# PCB.net
KiCad netlist of a schematic drawn in EasyEDA Pro
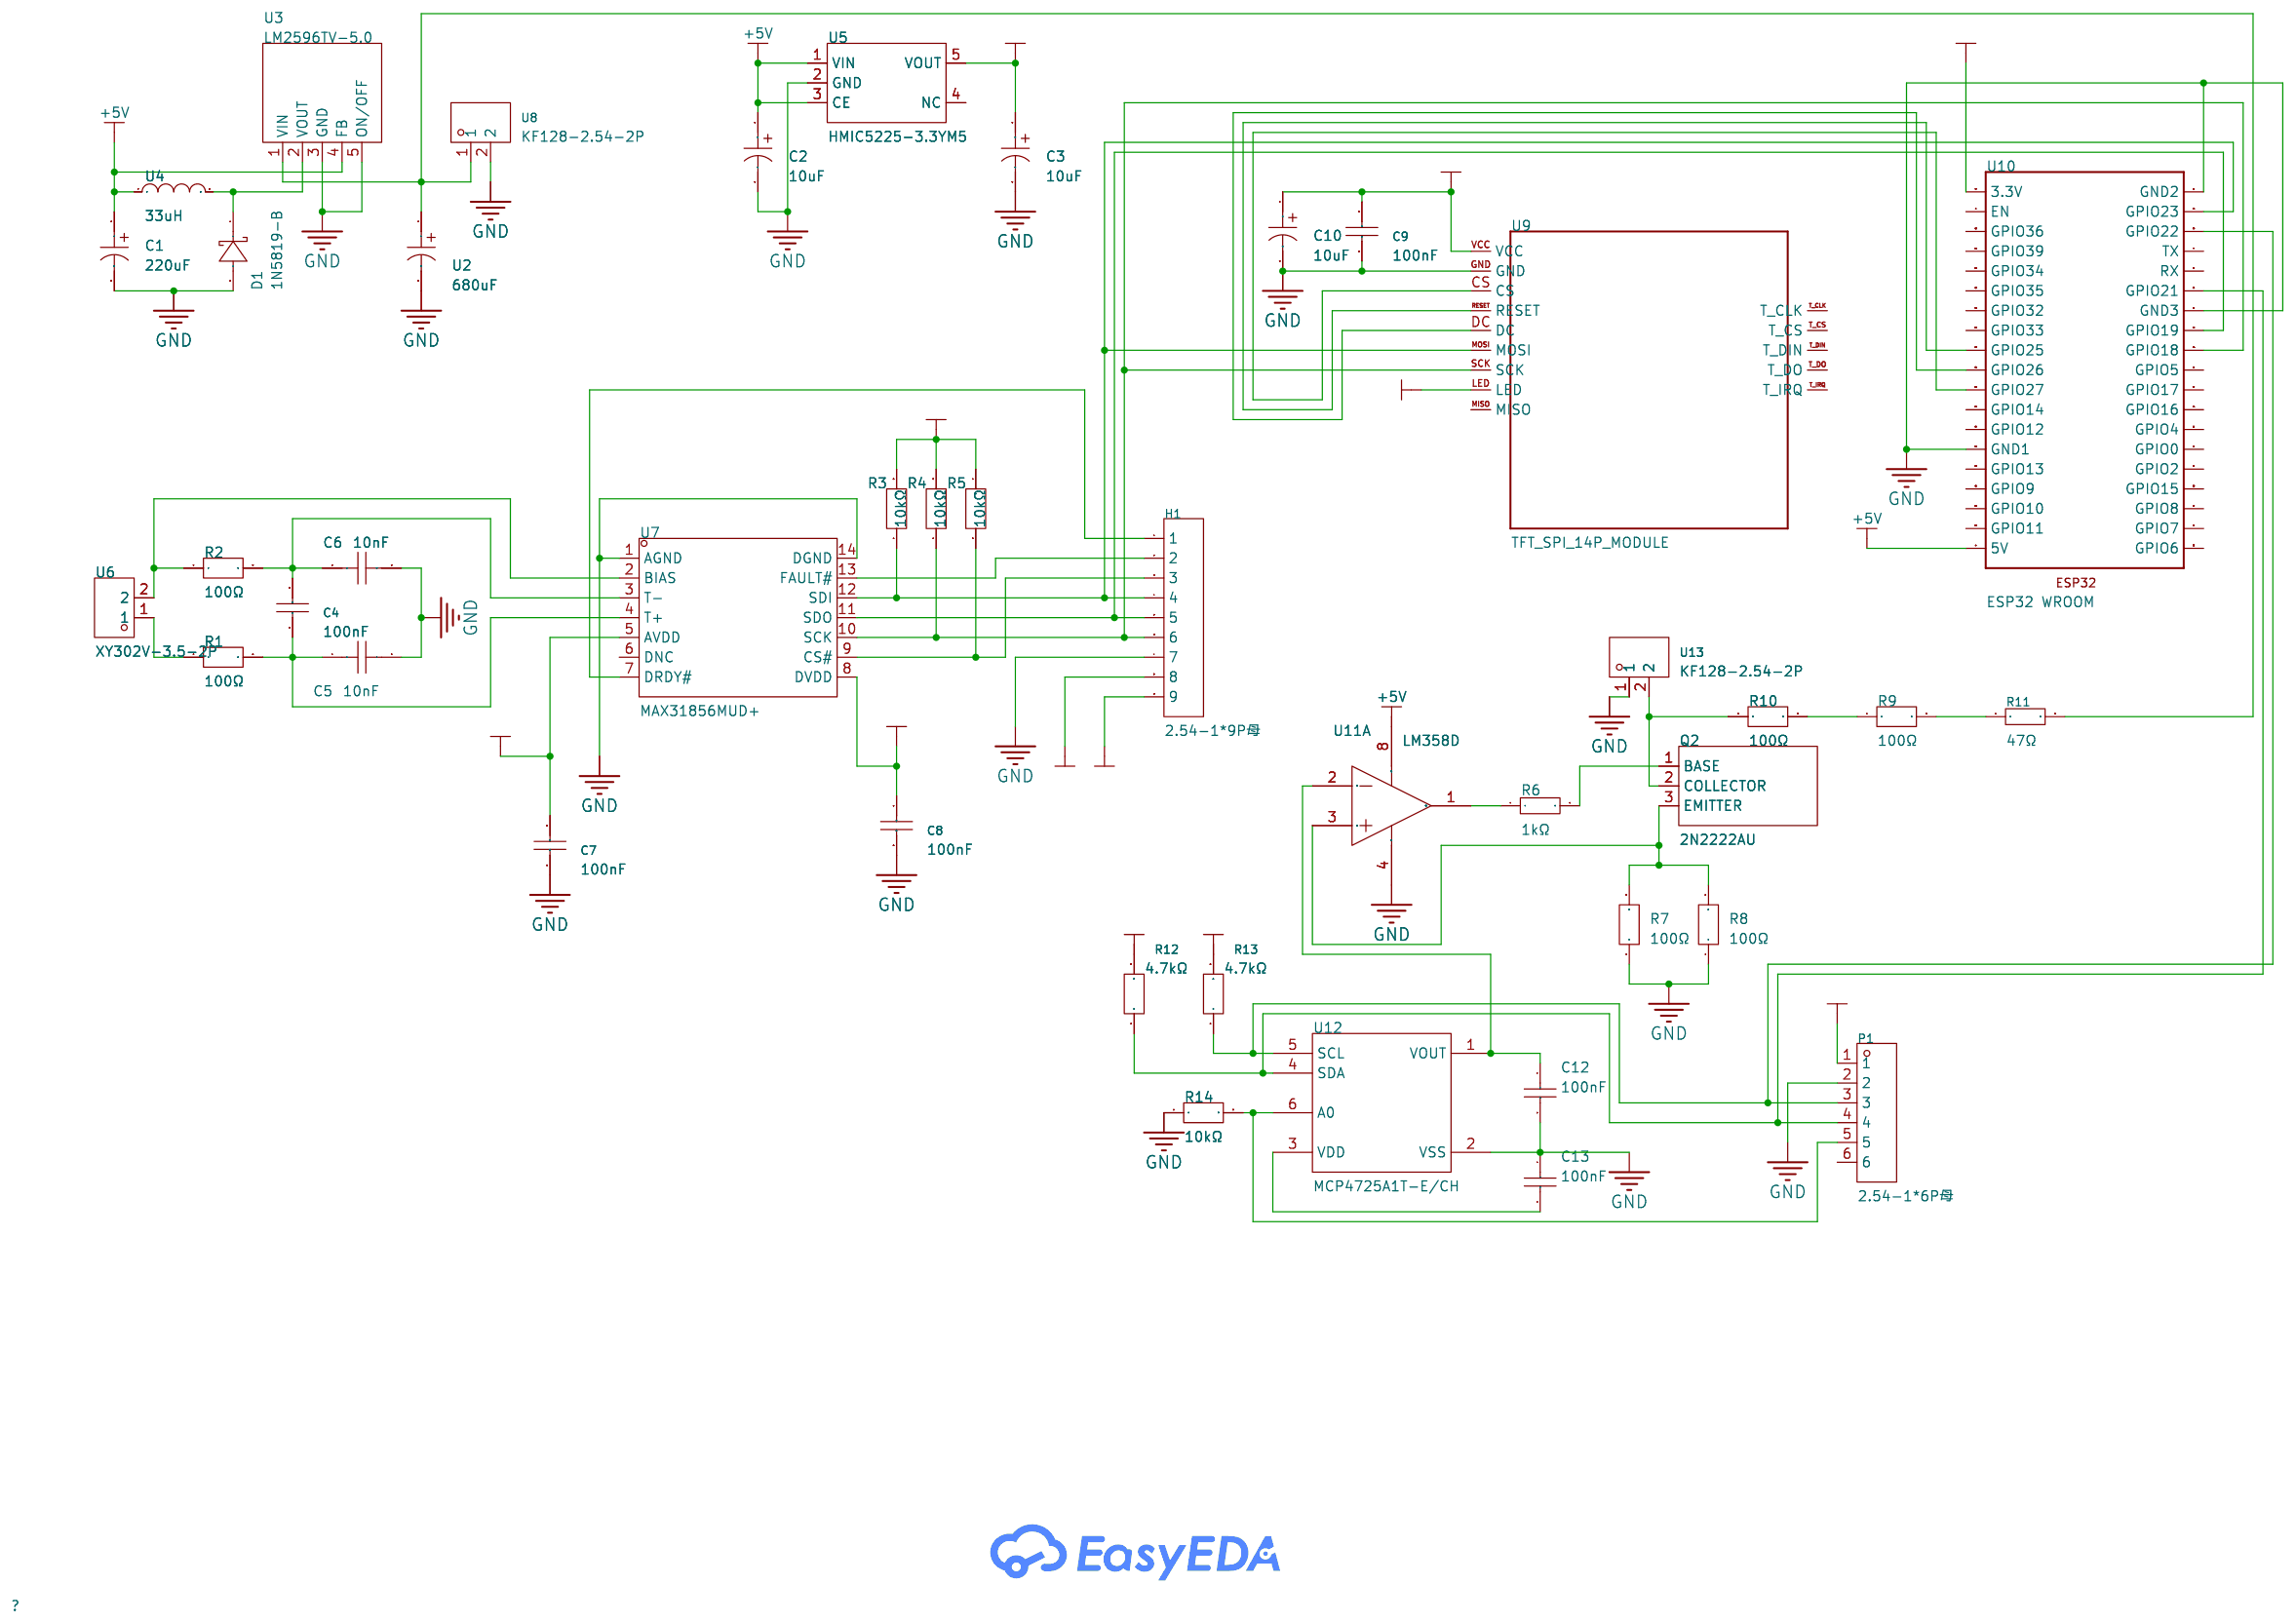
[diagram p0: schematic sheet]

(export (version "E")
  (design (tool "Eeschema 10.0.6"))
  (components
    (comp (ref "C1")
      (value "220uF")
      (footprint "easyedapro:CAP-TH_BD10.0-P5.00-D1.0-FD")
      (fields
        (field (name "Manufacturer Part") "220uF50V10x13GF")
        (field (name "Manufacturer") "Econd(米朗电子)")
      )
      (libsource (lib "easyedapro") (part "220UF50V10X13GF"))
    )
    (comp (ref "C2")
      (value "10uF")
      (footprint "easyedapro:CAP-TH_BD5.0-P2.00-D0.8-FD-10UF50VC110GL")
      (fields (field (name "Manufacturer Part") "10UF50VC110GL") (field (name "Manufacturer") "Econd(米朗电子)"))
      (libsource (lib "easyedapro") (part "10UF50VC110GL"))
    )
    (comp (ref "C3")
      (value "10uF")
      (footprint "easyedapro:CAP-TH_BD5.0-P2.00-D0.8-FD-10UF50VC110GL")
      (fields (field (name "Manufacturer Part") "10UF50VC110GL") (field (name "Manufacturer") "Econd(米朗电子)"))
      (libsource (lib "easyedapro") (part "10UF50VC110GL"))
    )
    (comp (ref "C4")
      (value "100nF")
      (footprint "easyedapro:C0805")
      (description "Capacitance:100nF Tolerance:±10% Tolerance:±10% Voltage Rating:50V Temperature Coefficient:X7R")
      (fields (field (name "Manufacturer Part") "0805B104K500NT") (field (name "Manufacturer") "FH(风华)"))
      (libsource (lib "easyedapro") (part "0805B104K500NT"))
    )
    (comp (ref "C5")
      (value "10nF")
      (footprint "easyedapro:C0402")
      (description "Capacitance:10nF Tolerance:±10% Tolerance:±10% Voltage Rating:50V Temperature Coefficient:X7R")
      (fields
        (field (name "Manufacturer Part") "FCC0402B103K500AT")
        (field (name "Manufacturer") "FOJAN(富捷)")
      )
      (libsource (lib "easyedapro") (part "FCC0402B103K500AT"))
    )
    (comp (ref "C6")
      (value "10nF")
      (footprint "easyedapro:C0402")
      (description "Capacitance:10nF Tolerance:±10% Tolerance:±10% Voltage Rating:50V Temperature Coefficient:X7R")
      (fields
        (field (name "Manufacturer Part") "FCC0402B103K500AT")
        (field (name "Manufacturer") "FOJAN(富捷)")
      )
      (libsource (lib "easyedapro") (part "FCC0402B103K500AT"))
    )
    (comp (ref "C7")
      (value "100nF")
      (footprint "easyedapro:C0805")
      (description "Capacitance:100nF Tolerance:±10% Tolerance:±10% Voltage Rating:50V Temperature Coefficient:X7R")
      (fields (field (name "Manufacturer Part") "0805B104K500NT") (field (name "Manufacturer") "FH(风华)"))
      (libsource (lib "easyedapro") (part "0805B104K500NT"))
    )
    (comp (ref "C8")
      (value "100nF")
      (footprint "easyedapro:C0805")
      (description "Capacitance:100nF Tolerance:±10% Tolerance:±10% Voltage Rating:50V Temperature Coefficient:X7R")
      (fields (field (name "Manufacturer Part") "0805B104K500NT") (field (name "Manufacturer") "FH(风华)"))
      (libsource (lib "easyedapro") (part "0805B104K500NT"))
    )
    (comp (ref "C9")
      (value "100nF")
      (footprint "easyedapro:C0805")
      (description "Capacitance:100nF Tolerance:±10% Tolerance:±10% Voltage Rating:50V Temperature Coefficient:X7R")
      (fields (field (name "Manufacturer Part") "0805B104K500NT") (field (name "Manufacturer") "FH(风华)"))
      (libsource (lib "easyedapro") (part "0805B104K500NT"))
    )
    (comp (ref "C10")
      (value "10uF")
      (footprint "easyedapro:CAP-TH_BD5.0-P2.00-D0.8-FD-10UF50VC110GL")
      (fields (field (name "Manufacturer Part") "10UF50VC110GL") (field (name "Manufacturer") "Econd(米朗电子)"))
      (libsource (lib "easyedapro") (part "10UF50VC110GL"))
    )
    (comp (ref "C12")
      (value "100nF")
      (footprint "easyedapro:C0402")
      (description "Capacitance:100nF Tolerance:±10% Tolerance:±10% Voltage Rating:50V Temperature Coefficient:X7R")
      (fields (field (name "Manufacturer Part") "0402B104K500NT") (field (name "Manufacturer") "FH(风华)"))
      (libsource (lib "easyedapro") (part "0402B104K500NT"))
    )
    (comp (ref "C13")
      (value "100nF")
      (footprint "easyedapro:C0402")
      (description "Capacitance:100nF Tolerance:±10% Tolerance:±10% Voltage Rating:50V Temperature Coefficient:X7R")
      (fields (field (name "Manufacturer Part") "0402B104K500NT") (field (name "Manufacturer") "FH(风华)"))
      (libsource (lib "easyedapro") (part "0402B104K500NT"))
    )
    (comp (ref "D1")
      (value "1N5819-B")
      (footprint "easyedapro:DO-41_BD2.4-L4.7-P8.70-D0.6-RD")
      (fields (field (name "Manufacturer") "GOODWORK(固得沃克)"))
      (libsource (lib "easyedapro") (part "1N5819-B"))
    )
    (comp (ref "H1")
      (value "2.54-1*9P母")
      (footprint "easyedapro:HDR-TH_9P-P2.54-V-F-1")
      (fields (field (name "Manufacturer") "BOOMELE(博穆精密)"))
      (libsource (lib "easyedapro") (part "Header-Female-2.54_1x9"))
    )
    (comp (ref "P1")
      (value "2.54-1*6P母")
      (footprint "easyedapro:HDR-TH_6P-P2.54-V-F")
      (fields (field (name "Manufacturer") "BOOMELE(博穆精密)"))
      (libsource (lib "easyedapro") (part "Header-Female-2.54_1x6"))
    )
    (comp (ref "Q2")
      (value "2N2222AU")
      (footprint "easyedapro:SOT-89-3_L4.5-W2.4-P1.50-LS4.0-BR")
      (fields (field (name "Manufacturer") "CBI(创基)"))
      (libsource (lib "easyedapro") (part "2N2222AU"))
    )
    (comp (ref "R1")
      (value "100Ω")
      (footprint "easyedapro:R0603")
      (fields (field (name "Manufacturer Part") "FRC0603F1000TS") (field (name "Manufacturer") "FOJAN(富捷)"))
      (libsource (lib "easyedapro") (part "FRC0603F1000TS"))
    )
    (comp (ref "R2")
      (value "100Ω")
      (footprint "easyedapro:R0603")
      (fields (field (name "Manufacturer Part") "FRC0603F1000TS") (field (name "Manufacturer") "FOJAN(富捷)"))
      (libsource (lib "easyedapro") (part "FRC0603F1000TS"))
    )
    (comp (ref "R3")
      (value "10kΩ")
      (footprint "easyedapro:R0805")
      (fields (field (name "Manufacturer Part") "FRC0805J103TS") (field (name "Manufacturer") "FOJAN(富捷)"))
      (libsource (lib "easyedapro") (part "FRC0805J103TS"))
    )
    (comp (ref "R4")
      (value "10kΩ")
      (footprint "easyedapro:R0805")
      (fields (field (name "Manufacturer Part") "FRC0805J103TS") (field (name "Manufacturer") "FOJAN(富捷)"))
      (libsource (lib "easyedapro") (part "FRC0805J103TS"))
    )
    (comp (ref "R5")
      (value "10kΩ")
      (footprint "easyedapro:R0805")
      (fields (field (name "Manufacturer Part") "FRC0805J103TS") (field (name "Manufacturer") "FOJAN(富捷)"))
      (libsource (lib "easyedapro") (part "FRC0805J103TS"))
    )
    (comp (ref "R6")
      (value "1kΩ")
      (footprint "easyedapro:R0402")
      (fields (field (name "Manufacturer Part") "RC0402FR-071KL") (field (name "Manufacturer") "YAGEO(国巨)"))
      (libsource (lib "easyedapro") (part "RC0402FR-071KL"))
    )
    (comp (ref "R7")
      (value "100Ω")
      (footprint "easyedapro:R0603")
      (fields (field (name "Manufacturer Part") "FRC0603F1000TS") (field (name "Manufacturer") "FOJAN(富捷)"))
      (libsource (lib "easyedapro") (part "FRC0603F1000TS"))
    )
    (comp (ref "R8")
      (value "100Ω")
      (footprint "easyedapro:R0603")
      (fields (field (name "Manufacturer Part") "FRC0603F1000TS") (field (name "Manufacturer") "FOJAN(富捷)"))
      (libsource (lib "easyedapro") (part "FRC0603F1000TS"))
    )
    (comp (ref "R9")
      (value "100Ω")
      (footprint "easyedapro:R0603")
      (fields (field (name "Manufacturer Part") "FRC0603F1000TS") (field (name "Manufacturer") "FOJAN(富捷)"))
      (libsource (lib "easyedapro") (part "FRC0603F1000TS"))
    )
    (comp (ref "R10")
      (value "100Ω")
      (footprint "easyedapro:R0603")
      (fields (field (name "Manufacturer Part") "FRC0603F1000TS") (field (name "Manufacturer") "FOJAN(富捷)"))
      (libsource (lib "easyedapro") (part "FRC0603F1000TS"))
    )
    (comp (ref "R11")
      (value "47Ω")
      (footprint "easyedapro:R0603")
      (fields
        (field (name "Manufacturer Part") "0603WAF470JT5E")
        (field (name "Manufacturer") "UNI-ROYAL(厚声)")
      )
      (libsource (lib "easyedapro") (part "0603WAF470JT5E"))
    )
    (comp (ref "R12")
      (value "4.7kΩ")
      (footprint "easyedapro:R0603")
      (fields (field (name "Manufacturer Part") "FRC0603J472 TS") (field (name "Manufacturer") "FOJAN(富捷)"))
      (libsource (lib "easyedapro") (part "FRC0603J472 TS"))
    )
    (comp (ref "R13")
      (value "4.7kΩ")
      (footprint "easyedapro:R0603")
      (fields (field (name "Manufacturer Part") "FRC0603J472 TS") (field (name "Manufacturer") "FOJAN(富捷)"))
      (libsource (lib "easyedapro") (part "FRC0603J472 TS"))
    )
    (comp (ref "R14")
      (value "10kΩ")
      (footprint "easyedapro:R0805")
      (fields (field (name "Manufacturer Part") "FRC0805J103TS") (field (name "Manufacturer") "FOJAN(富捷)"))
      (libsource (lib "easyedapro") (part "FRC0805J103TS"))
    )
    (comp (ref "U2")
      (value "680uF")
      (footprint "easyedapro:CAP-TH_BD13.0-P5.00-D0.6-FD")
      (fields
        (field (name "Manufacturer Part") "SHF680UF50V03EC1055")
        (field (name "Manufacturer") "KNSCHA(科尼盛)")
      )
      (libsource (lib "easyedapro") (part "SHF680UF50V03EC1055"))
    )
    (comp (ref "U3")
      (value "LM2596TV-5.0")
      (footprint "easyedapro:TO-220-5_L10.2-W4.5-P1.70-TL")
      (fields (field (name "Manufacturer") "HTC"))
      (libsource (lib "easyedapro") (part "LM2596TV-5.0"))
    )
    (comp (ref "U4")
      (value "33uH")
      (footprint "easyedapro:IND-TH_L7.0-W4.0-P5.0")
      (fields (field (name "Manufacturer Part") "2727-07H") (field (name "Manufacturer") "API Delevan"))
      (libsource (lib "easyedapro") (part "2727-07H"))
    )
    (comp (ref "U5")
      (value "HMIC5225-3.3YM5")
      (footprint "easyedapro:SOT-23-5_L3.0-W1.7-P0.95-LS2.8-BL")
      (fields (field (name "Manufacturer") "HXY MOSFET(华轩阳电子)"))
      (libsource (lib "easyedapro") (part "HMIC5225-3.3YM5"))
    )
    (comp (ref "U6")
      (value "XY302V-3.5-2P")
      (footprint "easyedapro:CONN-TH_XY302V-3.5-2P")
      (fields (field (name "Manufacturer") "XINLAIYA(新莱亚)"))
      (libsource (lib "easyedapro") (part "XY302V-3.5-2P"))
    )
    (comp (ref "U7")
      (value "MAX31856MUD+")
      (footprint "easyedapro:TSSOP-14_L5.0-W4.4-P0.65-LS6.4-BL")
      (fields (field (name "Manufacturer") "ADI(亚德诺)/MAXIM(美信)"))
      (libsource (lib "easyedapro") (part "MAX31856MUD+"))
    )
    (comp (ref "U8")
      (value "KF128-2.54-2P")
      (footprint "easyedapro:CONN-TH_P2.54_KF128-2.54-2P")
      (fields (field (name "Manufacturer") "KEFA(科发)"))
      (libsource (lib "easyedapro") (part "KF128-2.54-2P"))
    )
    (comp (ref "U9")
      (value "TFT_SPI_14P_MODULE")
      (footprint "easyedapro:TFT_2_4_SPI_MODULE")
      (libsource (lib "easyedapro") (part "TFT_SPI_14P_MODULE"))
    )
    (comp (ref "U10")
      (value "ESP32 WROOM")
      (footprint "easyedapro:ESP32")
      (libsource (lib "easyedapro") (part "ESP32"))
    )
    (comp (ref "U11")
      (value "LM358D")
      (footprint "easyedapro:SO-8_L4.9-W3.9-P1.27-LS5.9-BL")
      (fields (field (name "Manufacturer") "ST(意法半导体)"))
      (libsource (lib "easyedapro") (part "LM358D_C2936099"))
    )
    (comp (ref "U12")
      (value "MCP4725A1T-E/CH")
      (footprint "easyedapro:SOT-23-6_L2.9-W1.6-P0.95-LS2.8-BR")
      (fields (field (name "Manufacturer") "MICROCHIP(美国微芯)"))
      (libsource (lib "easyedapro") (part "MCP4725A1T-E/CH"))
    )
    (comp (ref "U13")
      (value "KF128-2.54-2P")
      (footprint "easyedapro:CONN-TH_P2.54_KF128-2.54-2P")
      (fields (field (name "Manufacturer") "KEFA(科发)"))
      (libsource (lib "easyedapro") (part "KF128-2.54-2P"))
    )
  )
  (nets
    (net (code "1") (name "+3.3V") (class "Default")
      (node (ref "C10") (pin "1") (pinfunction "1_1") (pintype "input"))
      (node (ref "C3") (pin "1") (pinfunction "1_1") (pintype "input"))
      (node (ref "C7") (pin "1") (pinfunction "1_1") (pintype "input"))
      (node (ref "C8") (pin "1") (pinfunction "1_1") (pintype "input"))
      (node (ref "C9") (pin "1") (pinfunction "1_1") (pintype "input"))
      (node (ref "H1") (pin "8") (pinfunction "8_8") (pintype "input"))
      (node (ref "P1") (pin "1") (pinfunction "1_1") (pintype "input"))
      (node (ref "R12") (pin "2") (pinfunction "2_2") (pintype "input"))
      (node (ref "R13") (pin "2") (pinfunction "2_2") (pintype "input"))
      (node (ref "R3") (pin "2") (pinfunction "2_2") (pintype "unspecified"))
      (node (ref "R4") (pin "2") (pinfunction "2_2") (pintype "unspecified"))
      (node (ref "R5") (pin "1") (pinfunction "1_1") (pintype "unspecified"))
      (node (ref "U10") (pin "3.3V") (pinfunction "3.3V_3.3V") (pintype "bidirectional"))
      (node (ref "U5") (pin "5") (pinfunction "VOUT_5") (pintype "unspecified"))
      (node (ref "U7") (pin "5") (pinfunction "AVDD_5") (pintype "unspecified"))
      (node (ref "U7") (pin "8") (pinfunction "DVDD_8") (pintype "unspecified"))
      (node (ref "U9") (pin "LED") (pinfunction "LED_LED") (pintype "input"))
      (node (ref "U9") (pin "VCC") (pinfunction "VCC_VCC") (pintype "unspecified"))
    )
    (net (code "2") (name "+5V") (class "Default")
      (node (ref "C1") (pin "1") (pinfunction "1_1") (pintype "input"))
      (node (ref "C2") (pin "1") (pinfunction "1_1") (pintype "input"))
      (node (ref "U10") (pin "5V") (pinfunction "5V_5V") (pintype "bidirectional"))
      (node (ref "U11") (pin "8") (pinfunction "VCC+_8") (pintype "unspecified"))
      (node (ref "U3") (pin "4") (pinfunction "FB_4") (pintype "unspecified"))
      (node (ref "U4") (pin "1") (pinfunction "1_1") (pintype "unspecified"))
      (node (ref "U5") (pin "1") (pinfunction "VIN_1") (pintype "unspecified"))
      (node (ref "U5") (pin "3") (pinfunction "CE_3") (pintype "unspecified"))
    )
    (net (code "3") (name "GND") (class "Default")
      (node (ref "C1") (pin "2") (pinfunction "2_2") (pintype "input"))
      (node (ref "C10") (pin "2") (pinfunction "2_2") (pintype "input"))
      (node (ref "C12") (pin "2") (pinfunction "2_2") (pintype "input"))
      (node (ref "C13") (pin "1") (pinfunction "1_1") (pintype "input"))
      (node (ref "C2") (pin "2") (pinfunction "2_2") (pintype "input"))
      (node (ref "C3") (pin "2") (pinfunction "2_2") (pintype "input"))
      (node (ref "C5") (pin "2") (pinfunction "2_2") (pintype "unspecified"))
      (node (ref "C6") (pin "2") (pinfunction "2_2") (pintype "unspecified"))
      (node (ref "C7") (pin "2") (pinfunction "2_2") (pintype "input"))
      (node (ref "C8") (pin "2") (pinfunction "2_2") (pintype "input"))
      (node (ref "C9") (pin "2") (pinfunction "2_2") (pintype "input"))
      (node (ref "D1") (pin "2") (pinfunction "A_2") (pintype "unspecified"))
      (node (ref "H1") (pin "7") (pinfunction "7_7") (pintype "input"))
      (node (ref "P1") (pin "2") (pinfunction "2_2") (pintype "input"))
      (node (ref "R14") (pin "1") (pinfunction "1_1") (pintype "unspecified"))
      (node (ref "R7") (pin "1") (pinfunction "1_1") (pintype "unspecified"))
      (node (ref "R8") (pin "1") (pinfunction "1_1") (pintype "unspecified"))
      (node (ref "U10") (pin "GND1") (pinfunction "GND1_GND1") (pintype "bidirectional"))
      (node (ref "U10") (pin "GND2") (pinfunction "GND2_GND2") (pintype "bidirectional"))
      (node (ref "U10") (pin "GND3") (pinfunction "GND3_GND3") (pintype "bidirectional"))
      (node (ref "U11") (pin "4") (pinfunction "VCC-_4") (pintype "unspecified"))
      (node (ref "U12") (pin "2") (pinfunction "VSS_2") (pintype "unspecified"))
      (node (ref "U13") (pin "1") (pinfunction "1_1") (pintype "input"))
      (node (ref "U2") (pin "2") (pinfunction "2_2") (pintype "input"))
      (node (ref "U3") (pin "3") (pinfunction "GND_3") (pintype "unspecified"))
      (node (ref "U3") (pin "5") (pinfunction "ON/OFF_5") (pintype "unspecified"))
      (node (ref "U5") (pin "2") (pinfunction "GND_2") (pintype "unspecified"))
      (node (ref "U7") (pin "1") (pinfunction "AGND_1") (pintype "unspecified"))
      (node (ref "U7") (pin "14") (pinfunction "DGND_14") (pintype "unspecified"))
      (node (ref "U8") (pin "2") (pinfunction "2_2") (pintype "input"))
      (node (ref "U9") (pin "GND") (pinfunction "GND_GND") (pintype "unspecified"))
    )
    (net (code "4") (name "Net-(D1-K)") (class "Default")
      (node (ref "D1") (pin "1") (pinfunction "K_1") (pintype "unspecified"))
      (node (ref "U3") (pin "2") (pinfunction "VOUT_2") (pintype "unspecified"))
      (node (ref "U4") (pin "2") (pinfunction "2_2") (pintype "unspecified"))
    )
    (net (code "5") (name "Net-(Q2-BASE)") (class "Default")
      (node (ref "Q2") (pin "1") (pinfunction "BASE_1") (pintype "unspecified"))
      (node (ref "R6") (pin "2") (pinfunction "2_2") (pintype "input"))
    )
    (net (code "6") (name "Net-(Q2-COLLECTOR)") (class "Default")
      (node (ref "Q2") (pin "2") (pinfunction "COLLECTOR_2") (pintype "unspecified"))
      (node (ref "R10") (pin "1") (pinfunction "1_1") (pintype "unspecified"))
      (node (ref "U13") (pin "2") (pinfunction "2_2") (pintype "input"))
    )
    (net (code "7") (name "Net-(Q2-EMITTER)") (class "Default")
      (node (ref "Q2") (pin "3") (pinfunction "EMITTER_3") (pintype "unspecified"))
      (node (ref "R7") (pin "2") (pinfunction "2_2") (pintype "unspecified"))
      (node (ref "R8") (pin "2") (pinfunction "2_2") (pintype "unspecified"))
      (node (ref "U11") (pin "3") (pinfunction "IN1+_3") (pintype "unspecified"))
    )
    (net (code "8") (name "Net-(R1-Pad1)") (class "Default")
      (node (ref "R1") (pin "1") (pinfunction "1_1") (pintype "unspecified"))
      (node (ref "U6") (pin "1") (pinfunction "1_1") (pintype "unspecified"))
    )
    (net (code "9") (name "Net-(R10-Pad2)") (class "Default")
      (node (ref "R10") (pin "2") (pinfunction "2_2") (pintype "unspecified"))
      (node (ref "R9") (pin "1") (pinfunction "1_1") (pintype "unspecified"))
    )
    (net (code "10") (name "Net-(R11-Pad1)") (class "Default")
      (node (ref "R11") (pin "1") (pinfunction "1_1") (pintype "input"))
      (node (ref "R9") (pin "2") (pinfunction "2_2") (pintype "unspecified"))
    )
    (net (code "11") (name "Net-(U3-VIN)") (class "Default")
      (node (ref "R11") (pin "2") (pinfunction "2_2") (pintype "input"))
      (node (ref "U2") (pin "1") (pinfunction "1_1") (pintype "input"))
      (node (ref "U3") (pin "1") (pinfunction "VIN_1") (pintype "unspecified"))
      (node (ref "U8") (pin "1") (pinfunction "1_1") (pintype "input"))
    )
    (net (code "12") (name "Net-(U7-BIAS)") (class "Default")
      (node (ref "R2") (pin "1") (pinfunction "1_1") (pintype "unspecified"))
      (node (ref "U6") (pin "2") (pinfunction "2_2") (pintype "unspecified"))
      (node (ref "U7") (pin "2") (pinfunction "BIAS_2") (pintype "unspecified"))
    )
    (net (code "13") (name "Net-(U7-CS#)") (class "Default")
      (node (ref "H1") (pin "3") (pinfunction "3_3") (pintype "input"))
      (node (ref "R5") (pin "2") (pinfunction "2_2") (pintype "unspecified"))
      (node (ref "U7") (pin "9") (pinfunction "CS#_9") (pintype "unspecified"))
    )
    (net (code "14") (name "Net-(U7-DRDY#)") (class "Default")
      (node (ref "H1") (pin "1") (pinfunction "1_1") (pintype "input"))
      (node (ref "U7") (pin "7") (pinfunction "DRDY#_7") (pintype "unspecified"))
    )
    (net (code "15") (name "Net-(U7-FAULT#)") (class "Default")
      (node (ref "H1") (pin "2") (pinfunction "2_2") (pintype "input"))
      (node (ref "U7") (pin "13") (pinfunction "FAULT#_13") (pintype "unspecified"))
    )
    (net (code "16") (name "Net-(U7-SCK)") (class "Default")
      (node (ref "H1") (pin "6") (pinfunction "6_6") (pintype "input"))
      (node (ref "R4") (pin "1") (pinfunction "1_1") (pintype "unspecified"))
      (node (ref "U10") (pin "GPIO18") (pinfunction "GPIO18_GPIO18") (pintype "bidirectional"))
      (node (ref "U7") (pin "10") (pinfunction "SCK_10") (pintype "unspecified"))
      (node (ref "U9") (pin "SCK") (pinfunction "SCK_SCK") (pintype "input"))
    )
    (net (code "17") (name "Net-(U7-SDI)") (class "Default")
      (node (ref "H1") (pin "4") (pinfunction "4_4") (pintype "input"))
      (node (ref "R3") (pin "1") (pinfunction "1_1") (pintype "unspecified"))
      (node (ref "U10") (pin "GPIO23") (pinfunction "GPIO23_GPIO23") (pintype "bidirectional"))
      (node (ref "U7") (pin "12") (pinfunction "SDI_12") (pintype "unspecified"))
      (node (ref "U9") (pin "MOSI") (pinfunction "MOSI_MOSI") (pintype "input"))
    )
    (net (code "18") (name "Net-(U7-SDO)") (class "Default")
      (node (ref "H1") (pin "5") (pinfunction "5_5") (pintype "input"))
      (node (ref "U10") (pin "GPIO19") (pinfunction "GPIO19_GPIO19") (pintype "bidirectional"))
      (node (ref "U7") (pin "11") (pinfunction "SDO_11") (pintype "unspecified"))
    )
    (net (code "19") (name "Net-(U7-T+)") (class "Default")
      (node (ref "C4") (pin "1") (pinfunction "1_1") (pintype "input"))
      (node (ref "C5") (pin "1") (pinfunction "1_1") (pintype "unspecified"))
      (node (ref "R1") (pin "2") (pinfunction "2_2") (pintype "unspecified"))
      (node (ref "U7") (pin "4") (pinfunction "T+_4") (pintype "unspecified"))
    )
    (net (code "20") (name "Net-(U7-T-)") (class "Default")
      (node (ref "C4") (pin "2") (pinfunction "2_2") (pintype "input"))
      (node (ref "C6") (pin "1") (pinfunction "1_1") (pintype "unspecified"))
      (node (ref "R2") (pin "2") (pinfunction "2_2") (pintype "unspecified"))
      (node (ref "U7") (pin "3") (pinfunction "T-_3") (pintype "unspecified"))
    )
    (net (code "21") (name "Net-(U10-PadGPIO25)") (class "Default")
      (node (ref "U10") (pin "GPIO25") (pinfunction "GPIO25_GPIO25") (pintype "bidirectional"))
      (node (ref "U9") (pin "RESET") (pinfunction "RESET_RESET") (pintype "input"))
    )
    (net (code "22") (name "Net-(U10-PadGPIO26)") (class "Default")
      (node (ref "U10") (pin "GPIO26") (pinfunction "GPIO26_GPIO26") (pintype "bidirectional"))
      (node (ref "U9") (pin "DC") (pinfunction "DC_DC") (pintype "input"))
    )
    (net (code "23") (name "Net-(U10-PadGPIO27)") (class "Default")
      (node (ref "U10") (pin "GPIO27") (pinfunction "GPIO27_GPIO27") (pintype "bidirectional"))
      (node (ref "U9") (pin "CS") (pinfunction "CS_CS") (pintype "input"))
    )
    (net (code "24") (name "Net-(U11A-IN1-)") (class "Default")
      (node (ref "C12") (pin "1") (pinfunction "1_1") (pintype "input"))
      (node (ref "U11") (pin "2") (pinfunction "IN1-_2") (pintype "unspecified"))
      (node (ref "U12") (pin "1") (pinfunction "VOUT_1") (pintype "output"))
    )
    (net (code "25") (name "Net-(U11A-OUT1)") (class "Default")
      (node (ref "R6") (pin "1") (pinfunction "1_1") (pintype "input"))
      (node (ref "U11") (pin "1") (pinfunction "OUT1_1") (pintype "unspecified"))
    )
    (net (code "26") (name "Net-(U12-A0)") (class "Default")
      (node (ref "P1") (pin "5") (pinfunction "5_5") (pintype "input"))
      (node (ref "R14") (pin "2") (pinfunction "2_2") (pintype "unspecified"))
      (node (ref "U12") (pin "6") (pinfunction "A0_6") (pintype "unspecified"))
    )
    (net (code "27") (name "Net-(U12-SCL)") (class "Default")
      (node (ref "P1") (pin "3") (pinfunction "3_3") (pintype "input"))
      (node (ref "R13") (pin "1") (pinfunction "1_1") (pintype "input"))
      (node (ref "U10") (pin "GPIO22") (pinfunction "GPIO22_GPIO22") (pintype "bidirectional"))
      (node (ref "U12") (pin "5") (pinfunction "SCL_5") (pintype "unspecified"))
    )
    (net (code "28") (name "Net-(U12-SDA)") (class "Default")
      (node (ref "P1") (pin "4") (pinfunction "4_4") (pintype "input"))
      (node (ref "R12") (pin "1") (pinfunction "1_1") (pintype "input"))
      (node (ref "U10") (pin "GPIO21") (pinfunction "GPIO21_GPIO21") (pintype "bidirectional"))
      (node (ref "U12") (pin "4") (pinfunction "SDA_4") (pintype "bidirectional"))
    )
    (net (code "29") (name "Net-(U12-VDD)") (class "Default")
      (node (ref "C13") (pin "2") (pinfunction "2_2") (pintype "input"))
      (node (ref "U12") (pin "3") (pinfunction "VDD_3") (pintype "unspecified"))
    )
    (net (code "30") (name "VIN") (class "Default")
      (node (ref "H1") (pin "9") (pinfunction "9_9") (pintype "input"))
    )
    (net (code "31") (name "unconnected-(P1-Pad6)") (class "Default")
      (node (ref "P1") (pin "6") (pinfunction "6_6") (pintype "input"))
    )
    (net (code "32") (name "unconnected-(U5-NC-Pad4)") (class "Default")
      (node (ref "U5") (pin "4") (pinfunction "NC_4") (pintype "unspecified"))
    )
    (net (code "33") (name "unconnected-(U7-DNC-Pad6)") (class "Default")
      (node (ref "U7") (pin "6") (pinfunction "DNC_6") (pintype "unspecified"))
    )
    (net (code "34") (name "unconnected-(U9-PadMISO)") (class "Default")
      (node (ref "U9") (pin "MISO") (pinfunction "MISO_MISO") (pintype "output"))
    )
    (net (code "35") (name "unconnected-(U9-PadT_CLK)") (class "Default")
      (node (ref "U9") (pin "T_CLK") (pinfunction "T_CLK_T_CLK") (pintype "input"))
    )
    (net (code "36") (name "unconnected-(U9-PadT_CS)") (class "Default")
      (node (ref "U9") (pin "T_CS") (pinfunction "T_CS_T_CS") (pintype "input"))
    )
    (net (code "37") (name "unconnected-(U9-PadT_DIN)") (class "Default")
      (node (ref "U9") (pin "T_DIN") (pinfunction "T_DIN_T_DIN") (pintype "input"))
    )
    (net (code "38") (name "unconnected-(U9-PadT_DO)") (class "Default")
      (node (ref "U9") (pin "T_DO") (pinfunction "T_DO_T_DO") (pintype "output"))
    )
    (net (code "39") (name "unconnected-(U9-PadT_IRQ)") (class "Default")
      (node (ref "U9") (pin "T_IRQ") (pinfunction "T_IRQ_T_IRQ") (pintype "output"))
    )
    (net (code "40") (name "unconnected-(U10-PadEN)") (class "Default")
      (node (ref "U10") (pin "EN") (pinfunction "EN_EN") (pintype "bidirectional"))
    )
    (net (code "41") (name "unconnected-(U10-PadGPIO0)") (class "Default")
      (node (ref "U10") (pin "GPIO0") (pinfunction "GPIO0_GPIO0") (pintype "bidirectional"))
    )
    (net (code "42") (name "unconnected-(U10-PadGPIO2)") (class "Default")
      (node (ref "U10") (pin "GPIO2") (pinfunction "GPIO2_GPIO2") (pintype "bidirectional"))
    )
    (net (code "43") (name "unconnected-(U10-PadGPIO4)") (class "Default")
      (node (ref "U10") (pin "GPIO4") (pinfunction "GPIO4_GPIO4") (pintype "bidirectional"))
    )
    (net (code "44") (name "unconnected-(U10-PadGPIO5)") (class "Default")
      (node (ref "U10") (pin "GPIO5") (pinfunction "GPIO5_GPIO5") (pintype "bidirectional"))
    )
    (net (code "45") (name "unconnected-(U10-PadGPIO6)") (class "Default")
      (node (ref "U10") (pin "GPIO6") (pinfunction "GPIO6_GPIO6") (pintype "bidirectional"))
    )
    (net (code "46") (name "unconnected-(U10-PadGPIO7)") (class "Default")
      (node (ref "U10") (pin "GPIO7") (pinfunction "GPIO7_GPIO7") (pintype "bidirectional"))
    )
    (net (code "47") (name "unconnected-(U10-PadGPIO8)") (class "Default")
      (node (ref "U10") (pin "GPIO8") (pinfunction "GPIO8_GPIO8") (pintype "bidirectional"))
    )
    (net (code "48") (name "unconnected-(U10-PadGPIO9)") (class "Default")
      (node (ref "U10") (pin "GPIO9") (pinfunction "GPIO9_GPIO9") (pintype "bidirectional"))
    )
    (net (code "49") (name "unconnected-(U10-PadGPIO10)") (class "Default")
      (node (ref "U10") (pin "GPIO10") (pinfunction "GPIO10_GPIO10") (pintype "bidirectional"))
    )
    (net (code "50") (name "unconnected-(U10-PadGPIO11)") (class "Default")
      (node (ref "U10") (pin "GPIO11") (pinfunction "GPIO11_GPIO11") (pintype "bidirectional"))
    )
    (net (code "51") (name "unconnected-(U10-PadGPIO12)") (class "Default")
      (node (ref "U10") (pin "GPIO12") (pinfunction "GPIO12_GPIO12") (pintype "bidirectional"))
    )
    (net (code "52") (name "unconnected-(U10-PadGPIO13)") (class "Default")
      (node (ref "U10") (pin "GPIO13") (pinfunction "GPIO13_GPIO13") (pintype "bidirectional"))
    )
    (net (code "53") (name "unconnected-(U10-PadGPIO14)") (class "Default")
      (node (ref "U10") (pin "GPIO14") (pinfunction "GPIO14_GPIO14") (pintype "bidirectional"))
    )
    (net (code "54") (name "unconnected-(U10-PadGPIO15)") (class "Default")
      (node (ref "U10") (pin "GPIO15") (pinfunction "GPIO15_GPIO15") (pintype "bidirectional"))
    )
    (net (code "55") (name "unconnected-(U10-PadGPIO16)") (class "Default")
      (node (ref "U10") (pin "GPIO16") (pinfunction "GPIO16_GPIO16") (pintype "bidirectional"))
    )
    (net (code "56") (name "unconnected-(U10-PadGPIO17)") (class "Default")
      (node (ref "U10") (pin "GPIO17") (pinfunction "GPIO17_GPIO17") (pintype "bidirectional"))
    )
    (net (code "57") (name "unconnected-(U10-PadGPIO32)") (class "Default")
      (node (ref "U10") (pin "GPIO32") (pinfunction "GPIO32_GPIO32") (pintype "bidirectional"))
    )
    (net (code "58") (name "unconnected-(U10-PadGPIO33)") (class "Default")
      (node (ref "U10") (pin "GPIO33") (pinfunction "GPIO33_GPIO33") (pintype "bidirectional"))
    )
    (net (code "59") (name "unconnected-(U10-PadGPIO34)") (class "Default")
      (node (ref "U10") (pin "GPIO34") (pinfunction "GPIO34_GPIO34") (pintype "bidirectional"))
    )
    (net (code "60") (name "unconnected-(U10-PadGPIO35)") (class "Default")
      (node (ref "U10") (pin "GPIO35") (pinfunction "GPIO35_GPIO35") (pintype "bidirectional"))
    )
    (net (code "61") (name "unconnected-(U10-PadGPIO36)") (class "Default")
      (node (ref "U10") (pin "GPIO36") (pinfunction "GPIO36_GPIO36") (pintype "bidirectional"))
    )
    (net (code "62") (name "unconnected-(U10-PadGPIO39)") (class "Default")
      (node (ref "U10") (pin "GPIO39") (pinfunction "GPIO39_GPIO39") (pintype "bidirectional"))
    )
    (net (code "63") (name "unconnected-(U10-PadRX)") (class "Default")
      (node (ref "U10") (pin "RX") (pinfunction "RX_RX") (pintype "bidirectional"))
    )
    (net (code "64") (name "unconnected-(U10-PadTX)") (class "Default")
      (node (ref "U10") (pin "TX") (pinfunction "TX_TX") (pintype "bidirectional"))
    )
  )
)
